# 65c02.net
KiCad netlist of a schematic drawn in Altium Designer
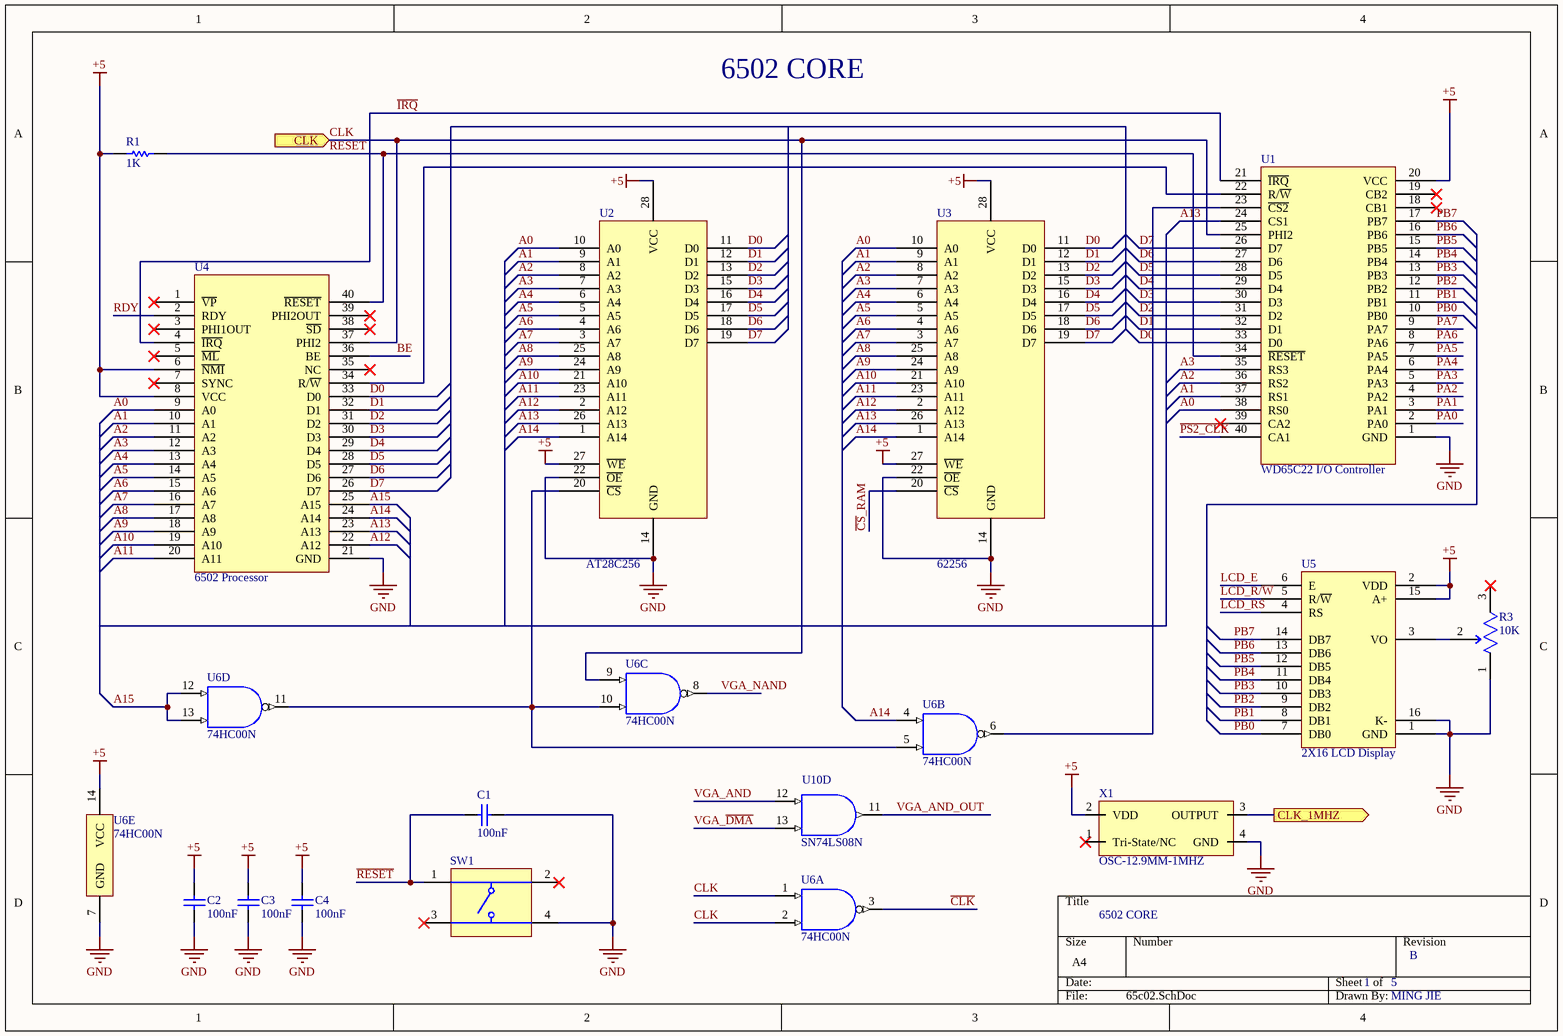
[diagram p0: 65c02.SchDoc]

(export (version "E")
  (design (tool "Eeschema 10.0.6"))
  (components
    (comp (ref "C1")
      (value "GRM21BR71H104KA01L")
      (footprint "CAPC2013X135X45ML10T25")
      (description "Chip Capacitor, 0.1 uF, +/- 10%, 50 V, -55 to 125 degC, 0805 (2012 Metric), RoHS, Tape and Reel")
      (fields
        (field (name "VOLTAGE") "50V")
        (field (name "CAPACITANCE") "100nF")
        (field (name "TOLERANCE") "10%")
      )
      (libsource (lib "Altium Content Vault") (part "CAP-NP-2"))
    )
    (comp (ref "C2")
      (value "GRM21BR71H104KA01L")
      (footprint "CAPC2013X135X45ML10T25")
      (description "Chip Capacitor, 0.1 uF, +/- 10%, 50 V, -55 to 125 degC, 0805 (2012 Metric), RoHS, Tape and Reel")
      (fields
        (field (name "VOLTAGE") "50V")
        (field (name "CAPACITANCE") "100nF")
        (field (name "TOLERANCE") "10%")
      )
      (libsource (lib "Altium Content Vault") (part "CAP-NP-2"))
    )
    (comp (ref "C3")
      (value "GRM21BR71H104KA01L")
      (footprint "CAPC2013X135X45ML10T25")
      (description "Chip Capacitor, 0.1 uF, +/- 10%, 50 V, -55 to 125 degC, 0805 (2012 Metric), RoHS, Tape and Reel")
      (fields
        (field (name "VOLTAGE") "50V")
        (field (name "CAPACITANCE") "100nF")
        (field (name "TOLERANCE") "10%")
      )
      (libsource (lib "Altium Content Vault") (part "CAP-NP-2"))
    )
    (comp (ref "C4")
      (value "GRM21BR71H104KA01L")
      (footprint "CAPC2013X135X45ML10T25")
      (description "Chip Capacitor, 0.1 uF, +/- 10%, 50 V, -55 to 125 degC, 0805 (2012 Metric), RoHS, Tape and Reel")
      (fields
        (field (name "VOLTAGE") "50V")
        (field (name "CAPACITANCE") "100nF")
        (field (name "TOLERANCE") "10%")
      )
      (libsource (lib "Altium Content Vault") (part "CAP-NP-2"))
    )
    (comp (ref "R1")
      (value "CRCW08051K00FKEA")
      (footprint "RESC2013X50X30NL20T20")
      (fields (field (name "MANUFACTURER") "Vishay Dale") (field (name "RESISTANCE") "1K"))
      (libsource (lib "Altium Content Vault") (part "RES"))
    )
    (comp (ref "R3")
      (value "3296W-1-103RLF")
      (footprint "FP-3296W-MFG")
      (description "TRIMMER 10K OHM 0.5W PC PIN TOP")
      (fields (field (name "RESISTANCE") "10K") (field (name "TOLERANCE") "10%"))
      (libsource (lib "Altium Content Vault") (part "194907ebf2981c0cdd5d9631a0af656"))
    )
    (comp (ref "SW1")
      (value "K2-1102SP-C4SC-04")
      (footprint "TECO-FSM4JSMA_V")
      (description "Swicth, SPST, 24 V, -35 to 85 degC, 4-Pin SMD, RoHS, Tape and Reel")
      (fields (field (name "MANUFACTURER") "TE Connectivity"))
      (libsource (lib "Altium Content Vault") (part "SW-SPST-4_A"))
    )
    (comp (ref "U1")
      (value "WD65C22 I/O Controller")
      (footprint "PDIP_40")
      (description "WD65C22 PDIP-40, I/O Controller")
      (libsource (lib "6502_lib") (part "WD65C22"))
    )
    (comp (ref "U2")
      (value "AT28C256")
      (footprint "DIP_28")
      (description "Paged Parallel EEPROM AT28C256")
      (libsource (lib "6502_lib") (part "AT28C256"))
    )
    (comp (ref "U3")
      (value "62256")
      (footprint "DIP_28")
      (description "32K x 8, SRAM")
      (libsource (lib "6502_lib") (part "62256"))
    )
    (comp (ref "U4")
      (value "6502 Processor")
      (footprint "PDIP_40")
      (description "WDC 6502 PDIP-40")
      (libsource (lib "6502_lib") (part "WDC65C02"))
    )
    (comp (ref "U5")
      (value "2X16 LCD Display")
      (footprint "LCD_2x16")
      (description "2X16 LCD Display, Parallel input")
      (libsource (lib "6502_lib") (part "LCM1602C"))
    )
    (comp (ref "U6")
      (value "74HC00N")
      (footprint "NXP-SOT27-1-14")
      (description "Quad 2-input NAND gate, CMOS, 2 to 6 V, -40 to 125 degC, 14-Pin DIP (SOT27-1), RoHS, Bulk")
      (fields (field (name "MANUFACTURER") "NXP Semiconductors"))
      (libsource (lib "") (part "NXP-74HC00N_HCT00N-DIP-14_1"))
    )
    (comp (ref "U10")
      (value "SN74LS08N")
      (footprint "N0014A")
      (description "Quadruple 2-Input Positive-AND Gates, N0014A, TUBE")
      (fields
        (field (name "MANUFACTURER") "Texas Instruments")
        (field (name "GENERIC PART NUMBER") "SN74LS08")
      )
      (libsource (lib "Altium Content Vault") (part "TI-AND-4-2IN-14"))
    )
    (comp (ref "X1")
      (value "OSC-12.9MM-1MHZ")
      (footprint "OSC_THT_12-9MM")
      (description "12.9MM x 12.9MM, 1MHz Can Oscillator")
      (libsource (lib "6502_lib") (part "OSC-12.9MM-1MHZ"))
    )
  )
  (nets
    (net (code "1") (name "+5") (class "Default")
      (node (ref "C2") (pin "1") (pinfunction "1_1") (pintype "passive"))
      (node (ref "C3") (pin "1") (pinfunction "1_1") (pintype "passive"))
      (node (ref "C4") (pin "1") (pinfunction "1_1") (pintype "passive"))
      (node (ref "R1") (pin "1") (pinfunction "1_1") (pintype "passive"))
      (node (ref "U1") (pin "20") (pinfunction "VCC_20") (pintype "passive"))
      (node (ref "U2") (pin "27") (pinfunction "~{WE}_27") (pintype "passive"))
      (node (ref "U2") (pin "28") (pinfunction "VCC_28") (pintype "passive"))
      (node (ref "U3") (pin "27") (pinfunction "~{WE}_27") (pintype "passive"))
      (node (ref "U3") (pin "28") (pinfunction "VCC_28") (pintype "passive"))
      (node (ref "U4") (pin "6") (pinfunction "~{NMI}_6") (pintype "passive"))
      (node (ref "U4") (pin "8") (pinfunction "VCC_8") (pintype "passive"))
      (node (ref "U5") (pin "15") (pinfunction "A+_15") (pintype "passive"))
      (node (ref "U5") (pin "2") (pinfunction "VDD_2") (pintype "passive"))
      (node (ref "U6") (pin "14") (pinfunction "VCC_14") (pintype "power_in"))
      (node (ref "X1") (pin "2") (pinfunction "VDD_2") (pintype "passive"))
    )
    (net (code "2") (name "/A0") (class "Default")
      (node (ref "U1") (pin "38") (pinfunction "RS0_38") (pintype "passive"))
      (node (ref "U2") (pin "10") (pinfunction "A0_10") (pintype "passive"))
      (node (ref "U3") (pin "10") (pinfunction "A0_10") (pintype "passive"))
      (node (ref "U4") (pin "9") (pinfunction "A0_9") (pintype "passive"))
    )
    (net (code "3") (name "/A1") (class "Default")
      (node (ref "U1") (pin "37") (pinfunction "RS1_37") (pintype "passive"))
      (node (ref "U2") (pin "9") (pinfunction "A1_9") (pintype "passive"))
      (node (ref "U3") (pin "9") (pinfunction "A1_9") (pintype "passive"))
      (node (ref "U4") (pin "10") (pinfunction "A1_10") (pintype "passive"))
    )
    (net (code "4") (name "/A2") (class "Default")
      (node (ref "U1") (pin "36") (pinfunction "RS2_36") (pintype "passive"))
      (node (ref "U2") (pin "8") (pinfunction "A2_8") (pintype "passive"))
      (node (ref "U3") (pin "8") (pinfunction "A2_8") (pintype "passive"))
      (node (ref "U4") (pin "11") (pinfunction "A2_11") (pintype "passive"))
    )
    (net (code "5") (name "/A3") (class "Default")
      (node (ref "U1") (pin "35") (pinfunction "RS3_35") (pintype "passive"))
      (node (ref "U2") (pin "7") (pinfunction "A3_7") (pintype "passive"))
      (node (ref "U3") (pin "7") (pinfunction "A3_7") (pintype "passive"))
      (node (ref "U4") (pin "12") (pinfunction "A3_12") (pintype "passive"))
    )
    (net (code "6") (name "/A4") (class "Default")
      (node (ref "U2") (pin "6") (pinfunction "A4_6") (pintype "passive"))
      (node (ref "U3") (pin "6") (pinfunction "A4_6") (pintype "passive"))
      (node (ref "U4") (pin "13") (pinfunction "A4_13") (pintype "passive"))
    )
    (net (code "7") (name "/A5") (class "Default")
      (node (ref "U2") (pin "5") (pinfunction "A5_5") (pintype "passive"))
      (node (ref "U3") (pin "5") (pinfunction "A5_5") (pintype "passive"))
      (node (ref "U4") (pin "14") (pinfunction "A5_14") (pintype "passive"))
    )
    (net (code "8") (name "/A6") (class "Default")
      (node (ref "U2") (pin "4") (pinfunction "A6_4") (pintype "passive"))
      (node (ref "U3") (pin "4") (pinfunction "A6_4") (pintype "passive"))
      (node (ref "U4") (pin "15") (pinfunction "A6_15") (pintype "passive"))
    )
    (net (code "9") (name "/A7") (class "Default")
      (node (ref "U2") (pin "3") (pinfunction "A7_3") (pintype "passive"))
      (node (ref "U3") (pin "3") (pinfunction "A7_3") (pintype "passive"))
      (node (ref "U4") (pin "16") (pinfunction "A7_16") (pintype "passive"))
    )
    (net (code "10") (name "/A8") (class "Default")
      (node (ref "U2") (pin "25") (pinfunction "A8_25") (pintype "passive"))
      (node (ref "U3") (pin "25") (pinfunction "A8_25") (pintype "passive"))
      (node (ref "U4") (pin "17") (pinfunction "A8_17") (pintype "passive"))
    )
    (net (code "11") (name "/A9") (class "Default")
      (node (ref "U2") (pin "24") (pinfunction "A9_24") (pintype "passive"))
      (node (ref "U3") (pin "24") (pinfunction "A9_24") (pintype "passive"))
      (node (ref "U4") (pin "18") (pinfunction "A9_18") (pintype "passive"))
    )
    (net (code "12") (name "/A10") (class "Default")
      (node (ref "U2") (pin "21") (pinfunction "A10_21") (pintype "passive"))
      (node (ref "U3") (pin "21") (pinfunction "A10_21") (pintype "passive"))
      (node (ref "U4") (pin "19") (pinfunction "A10_19") (pintype "passive"))
    )
    (net (code "13") (name "/A11") (class "Default")
      (node (ref "U2") (pin "23") (pinfunction "A11_23") (pintype "passive"))
      (node (ref "U3") (pin "23") (pinfunction "A11_23") (pintype "passive"))
      (node (ref "U4") (pin "20") (pinfunction "A11_20") (pintype "passive"))
    )
    (net (code "14") (name "/A12") (class "Default")
      (node (ref "U2") (pin "2") (pinfunction "A12_2") (pintype "passive"))
      (node (ref "U3") (pin "2") (pinfunction "A12_2") (pintype "passive"))
      (node (ref "U4") (pin "22") (pinfunction "A12_22") (pintype "passive"))
    )
    (net (code "15") (name "/A13") (class "Default")
      (node (ref "U1") (pin "24") (pinfunction "CS1_24") (pintype "passive"))
      (node (ref "U2") (pin "26") (pinfunction "A13_26") (pintype "passive"))
      (node (ref "U3") (pin "26") (pinfunction "A13_26") (pintype "passive"))
      (node (ref "U4") (pin "23") (pinfunction "A13_23") (pintype "passive"))
    )
    (net (code "16") (name "/A14") (class "Default")
      (node (ref "U2") (pin "1") (pinfunction "A14_1") (pintype "passive"))
      (node (ref "U3") (pin "1") (pinfunction "A14_1") (pintype "passive"))
      (node (ref "U4") (pin "24") (pinfunction "A14_24") (pintype "passive"))
      (node (ref "U6") (pin "4") (pinfunction "2A_4") (pintype "input"))
    )
    (net (code "17") (name "/A15") (class "Default")
      (node (ref "U4") (pin "25") (pinfunction "A15_25") (pintype "passive"))
      (node (ref "U6") (pin "12") (pinfunction "4A_12") (pintype "input"))
      (node (ref "U6") (pin "13") (pinfunction "4B_13") (pintype "input"))
    )
    (net (code "18") (name "/BE") (class "Default")
      (node (ref "U4") (pin "36") (pinfunction "BE_36") (pintype "passive"))
    )
    (net (code "19") (name "/CLK") (class "Default")
      (node (ref "U1") (pin "25") (pinfunction "PHI2_25") (pintype "passive"))
      (node (ref "U4") (pin "37") (pinfunction "PHI2_37") (pintype "passive"))
      (node (ref "U6") (pin "1") (pinfunction "1A_1") (pintype "input"))
      (node (ref "U6") (pin "2") (pinfunction "1B_2") (pintype "input"))
      (node (ref "U6") (pin "9") (pinfunction "3A_9") (pintype "input"))
    )
    (net (code "20") (name "/CLK_1MHZ") (class "Default")
      (node (ref "X1") (pin "3") (pinfunction "OUTPUT_3") (pintype "passive"))
    )
    (net (code "21") (name "/D0") (class "Default")
      (node (ref "U1") (pin "33") (pinfunction "D0_33") (pintype "passive"))
      (node (ref "U2") (pin "11") (pinfunction "D0_11") (pintype "passive"))
      (node (ref "U3") (pin "11") (pinfunction "D0_11") (pintype "passive"))
      (node (ref "U4") (pin "33") (pinfunction "D0_33") (pintype "passive"))
    )
    (net (code "22") (name "/D1") (class "Default")
      (node (ref "U1") (pin "32") (pinfunction "D1_32") (pintype "passive"))
      (node (ref "U2") (pin "12") (pinfunction "D1_12") (pintype "passive"))
      (node (ref "U3") (pin "12") (pinfunction "D1_12") (pintype "passive"))
      (node (ref "U4") (pin "32") (pinfunction "D1_32") (pintype "passive"))
    )
    (net (code "23") (name "/D2") (class "Default")
      (node (ref "U1") (pin "31") (pinfunction "D2_31") (pintype "passive"))
      (node (ref "U2") (pin "13") (pinfunction "D2_13") (pintype "passive"))
      (node (ref "U3") (pin "13") (pinfunction "D2_13") (pintype "passive"))
      (node (ref "U4") (pin "31") (pinfunction "D2_31") (pintype "passive"))
    )
    (net (code "24") (name "/D3") (class "Default")
      (node (ref "U1") (pin "30") (pinfunction "D3_30") (pintype "passive"))
      (node (ref "U2") (pin "15") (pinfunction "D3_15") (pintype "passive"))
      (node (ref "U3") (pin "15") (pinfunction "D3_15") (pintype "passive"))
      (node (ref "U4") (pin "30") (pinfunction "D3_30") (pintype "passive"))
    )
    (net (code "25") (name "/D4") (class "Default")
      (node (ref "U1") (pin "29") (pinfunction "D4_29") (pintype "passive"))
      (node (ref "U2") (pin "16") (pinfunction "D4_16") (pintype "passive"))
      (node (ref "U3") (pin "16") (pinfunction "D4_16") (pintype "passive"))
      (node (ref "U4") (pin "29") (pinfunction "D4_29") (pintype "passive"))
    )
    (net (code "26") (name "/D5") (class "Default")
      (node (ref "U1") (pin "28") (pinfunction "D5_28") (pintype "passive"))
      (node (ref "U2") (pin "17") (pinfunction "D5_17") (pintype "passive"))
      (node (ref "U3") (pin "17") (pinfunction "D5_17") (pintype "passive"))
      (node (ref "U4") (pin "28") (pinfunction "D5_28") (pintype "passive"))
    )
    (net (code "27") (name "/D6") (class "Default")
      (node (ref "U1") (pin "27") (pinfunction "D6_27") (pintype "passive"))
      (node (ref "U2") (pin "18") (pinfunction "D6_18") (pintype "passive"))
      (node (ref "U3") (pin "18") (pinfunction "D6_18") (pintype "passive"))
      (node (ref "U4") (pin "27") (pinfunction "D6_27") (pintype "passive"))
    )
    (net (code "28") (name "/D7") (class "Default")
      (node (ref "U1") (pin "26") (pinfunction "D7_26") (pintype "passive"))
      (node (ref "U2") (pin "19") (pinfunction "D7_19") (pintype "passive"))
      (node (ref "U3") (pin "19") (pinfunction "D7_19") (pintype "passive"))
      (node (ref "U4") (pin "26") (pinfunction "D7_26") (pintype "passive"))
    )
    (net (code "29") (name "/LCD_E") (class "Default")
      (node (ref "U5") (pin "6") (pinfunction "E_6") (pintype "passive"))
    )
    (net (code "30") (name "/LCD_RS") (class "Default")
      (node (ref "U5") (pin "4") (pinfunction "RS_4") (pintype "passive"))
    )
    (net (code "31") (name "/LCD_R{slash}~{W}") (class "Default")
      (node (ref "U5") (pin "5") (pinfunction "R/~{W}_5") (pintype "passive"))
    )
    (net (code "32") (name "/PA0") (class "Default")
      (node (ref "U1") (pin "2") (pinfunction "PA0_2") (pintype "passive"))
    )
    (net (code "33") (name "/PA1") (class "Default")
      (node (ref "U1") (pin "3") (pinfunction "PA1_3") (pintype "passive"))
    )
    (net (code "34") (name "/PA2") (class "Default")
      (node (ref "U1") (pin "4") (pinfunction "PA2_4") (pintype "passive"))
    )
    (net (code "35") (name "/PA3") (class "Default")
      (node (ref "U1") (pin "5") (pinfunction "PA3_5") (pintype "passive"))
    )
    (net (code "36") (name "/PA4") (class "Default")
      (node (ref "U1") (pin "6") (pinfunction "PA4_6") (pintype "passive"))
    )
    (net (code "37") (name "/PA5") (class "Default")
      (node (ref "U1") (pin "7") (pinfunction "PA5_7") (pintype "passive"))
    )
    (net (code "38") (name "/PA6") (class "Default")
      (node (ref "U1") (pin "8") (pinfunction "PA6_8") (pintype "passive"))
    )
    (net (code "39") (name "/PA7") (class "Default")
      (node (ref "U1") (pin "9") (pinfunction "PA7_9") (pintype "passive"))
    )
    (net (code "40") (name "/PB0") (class "Default")
      (node (ref "U1") (pin "10") (pinfunction "PB0_10") (pintype "passive"))
      (node (ref "U5") (pin "7") (pinfunction "DB0_7") (pintype "passive"))
    )
    (net (code "41") (name "/PB1") (class "Default")
      (node (ref "U1") (pin "11") (pinfunction "PB1_11") (pintype "passive"))
      (node (ref "U5") (pin "8") (pinfunction "DB1_8") (pintype "passive"))
    )
    (net (code "42") (name "/PB2") (class "Default")
      (node (ref "U1") (pin "12") (pinfunction "PB2_12") (pintype "passive"))
      (node (ref "U5") (pin "9") (pinfunction "DB2_9") (pintype "passive"))
    )
    (net (code "43") (name "/PB3") (class "Default")
      (node (ref "U1") (pin "13") (pinfunction "PB3_13") (pintype "passive"))
      (node (ref "U5") (pin "10") (pinfunction "DB3_10") (pintype "passive"))
    )
    (net (code "44") (name "/PB4") (class "Default")
      (node (ref "U1") (pin "14") (pinfunction "PB4_14") (pintype "passive"))
      (node (ref "U5") (pin "11") (pinfunction "DB4_11") (pintype "passive"))
    )
    (net (code "45") (name "/PB5") (class "Default")
      (node (ref "U1") (pin "15") (pinfunction "PB5_15") (pintype "passive"))
      (node (ref "U5") (pin "12") (pinfunction "DB5_12") (pintype "passive"))
    )
    (net (code "46") (name "/PB6") (class "Default")
      (node (ref "U1") (pin "16") (pinfunction "PB6_16") (pintype "passive"))
      (node (ref "U5") (pin "13") (pinfunction "DB6_13") (pintype "passive"))
    )
    (net (code "47") (name "/PB7") (class "Default")
      (node (ref "U1") (pin "17") (pinfunction "PB7_17") (pintype "passive"))
      (node (ref "U5") (pin "14") (pinfunction "DB7_14") (pintype "passive"))
    )
    (net (code "48") (name "/RDY") (class "Default")
      (node (ref "U4") (pin "2") (pinfunction "RDY_2") (pintype "passive"))
    )
    (net (code "49") (name "/VGA_AND") (class "Default")
      (node (ref "U10") (pin "12") (pinfunction "4A_12") (pintype "input"))
    )
    (net (code "50") (name "/VGA_AND_OUT") (class "Default")
      (node (ref "U10") (pin "11") (pinfunction "4Y_11") (pintype "output"))
    )
    (net (code "51") (name "/VGA_NAND") (class "Default")
      (node (ref "U6") (pin "8") (pinfunction "~{3Y}_8") (pintype "output"))
    )
    (net (code "52") (name "/VGA_~{DMA}") (class "Default")
      (node (ref "U10") (pin "13") (pinfunction "4B_13") (pintype "input"))
    )
    (net (code "53") (name "/~{CLK}") (class "Default")
      (node (ref "U6") (pin "3") (pinfunction "~{1Y}_3") (pintype "output"))
    )
    (net (code "54") (name "/~{CS}_RAM") (class "Default")
      (node (ref "U3") (pin "20") (pinfunction "~{CS}_20") (pintype "passive"))
    )
    (net (code "55") (name "/~{IRQ}") (class "Default")
      (node (ref "U1") (pin "21") (pinfunction "~{IRQ}_21") (pintype "passive"))
      (node (ref "U4") (pin "4") (pinfunction "~{IRQ}_4") (pintype "passive"))
    )
    (net (code "56") (name "/~{PS2_CLK}") (class "Default")
      (node (ref "U1") (pin "40") (pinfunction "CA1_40") (pintype "passive"))
    )
    (net (code "57") (name "/~{RESET}") (class "Default")
      (node (ref "C1") (pin "2") (pinfunction "2_2") (pintype "passive"))
      (node (ref "R1") (pin "2") (pinfunction "2_2") (pintype "passive"))
      (node (ref "SW1") (pin "1") (pinfunction "1_1") (pintype "passive"))
      (node (ref "U1") (pin "34") (pinfunction "~{RESET}_34") (pintype "passive"))
      (node (ref "U4") (pin "40") (pinfunction "~{RESET}_40") (pintype "passive"))
    )
    (net (code "58") (name "GND") (class "Default")
      (node (ref "C1") (pin "1") (pinfunction "1_1") (pintype "passive"))
      (node (ref "C2") (pin "2") (pinfunction "2_2") (pintype "passive"))
      (node (ref "C3") (pin "2") (pinfunction "2_2") (pintype "passive"))
      (node (ref "C4") (pin "2") (pinfunction "2_2") (pintype "passive"))
      (node (ref "R3") (pin "1") (pinfunction "CCW_1") (pintype "passive"))
      (node (ref "SW1") (pin "4") (pinfunction "4_4") (pintype "passive"))
      (node (ref "U1") (pin "1") (pinfunction "GND_1") (pintype "passive"))
      (node (ref "U2") (pin "14") (pinfunction "GND_14") (pintype "passive"))
      (node (ref "U2") (pin "22") (pinfunction "~{OE}_22") (pintype "passive"))
      (node (ref "U3") (pin "14") (pinfunction "GND_14") (pintype "passive"))
      (node (ref "U3") (pin "22") (pinfunction "~{OE}_22") (pintype "passive"))
      (node (ref "U4") (pin "21") (pinfunction "GND_21") (pintype "passive"))
      (node (ref "U5") (pin "1") (pinfunction "GND_1") (pintype "passive"))
      (node (ref "U5") (pin "16") (pinfunction "K-_16") (pintype "passive"))
      (node (ref "U6") (pin "7") (pinfunction "GND_7") (pintype "power_in"))
      (node (ref "X1") (pin "4") (pinfunction "GND_4") (pintype "passive"))
    )
    (net (code "59") (name "Net-(R3-WIPER)") (class "Default")
      (node (ref "R3") (pin "2") (pinfunction "WIPER_2") (pintype "passive"))
      (node (ref "U5") (pin "3") (pinfunction "VO_3") (pintype "passive"))
    )
    (net (code "60") (name "Net-(U1-R{slash}~{W})") (class "Default")
      (node (ref "U1") (pin "22") (pinfunction "R/~{W}_22") (pintype "passive"))
      (node (ref "U4") (pin "34") (pinfunction "R/~{W}_34") (pintype "passive"))
    )
    (net (code "61") (name "Net-(U1-~{CS2})") (class "Default")
      (node (ref "U1") (pin "23") (pinfunction "~{CS2}_23") (pintype "passive"))
      (node (ref "U6") (pin "6") (pinfunction "~{2Y}_6") (pintype "output"))
    )
    (net (code "62") (name "Net-(U2-~{CS})") (class "Default")
      (node (ref "U2") (pin "20") (pinfunction "~{CS}_20") (pintype "passive"))
      (node (ref "U6") (pin "10") (pinfunction "3B_10") (pintype "input"))
      (node (ref "U6") (pin "11") (pinfunction "~{4Y}_11") (pintype "output"))
      (node (ref "U6") (pin "5") (pinfunction "2B_5") (pintype "input"))
    )
    (net (code "63") (name "unconnected-(R3-CW-Pad3)") (class "Default")
      (node (ref "R3") (pin "3") (pinfunction "CW_3") (pintype "passive+no_connect"))
    )
    (net (code "64") (name "unconnected-(SW1-Pad2)") (class "Default")
      (node (ref "SW1") (pin "2") (pinfunction "2_2") (pintype "passive+no_connect"))
    )
    (net (code "65") (name "unconnected-(SW1-Pad3)") (class "Default")
      (node (ref "SW1") (pin "3") (pinfunction "3_3") (pintype "passive+no_connect"))
    )
    (net (code "66") (name "unconnected-(U1-CA2-Pad39)") (class "Default")
      (node (ref "U1") (pin "39") (pinfunction "CA2_39") (pintype "passive+no_connect"))
    )
    (net (code "67") (name "unconnected-(U1-CB1-Pad18)") (class "Default")
      (node (ref "U1") (pin "18") (pinfunction "CB1_18") (pintype "passive+no_connect"))
    )
    (net (code "68") (name "unconnected-(U1-CB2-Pad19)") (class "Default")
      (node (ref "U1") (pin "19") (pinfunction "CB2_19") (pintype "passive+no_connect"))
    )
    (net (code "69") (name "unconnected-(U4-NC-Pad35)") (class "Default")
      (node (ref "U4") (pin "35") (pinfunction "NC_35") (pintype "passive+no_connect"))
    )
    (net (code "70") (name "unconnected-(U4-PHI1OUT-Pad3)") (class "Default")
      (node (ref "U4") (pin "3") (pinfunction "PHI1OUT_3") (pintype "passive+no_connect"))
    )
    (net (code "71") (name "unconnected-(U4-PHI2OUT-Pad39)") (class "Default")
      (node (ref "U4") (pin "39") (pinfunction "PHI2OUT_39") (pintype "passive+no_connect"))
    )
    (net (code "72") (name "unconnected-(U4-SYNC-Pad7)") (class "Default")
      (node (ref "U4") (pin "7") (pinfunction "SYNC_7") (pintype "passive+no_connect"))
    )
    (net (code "73") (name "unconnected-(U4-~{ML}-Pad5)") (class "Default")
      (node (ref "U4") (pin "5") (pinfunction "~{ML}_5") (pintype "passive+no_connect"))
    )
    (net (code "74") (name "unconnected-(U4-~{SD}-Pad38)") (class "Default")
      (node (ref "U4") (pin "38") (pinfunction "~{SD}_38") (pintype "passive+no_connect"))
    )
    (net (code "75") (name "unconnected-(U4-~{VP}-Pad1)") (class "Default")
      (node (ref "U4") (pin "1") (pinfunction "~{VP}_1") (pintype "passive+no_connect"))
    )
    (net (code "76") (name "unconnected-(X1-Tri-State{slash}NC-Pad1)") (class "Default")
      (node (ref "X1") (pin "1") (pinfunction "Tri-State/NC_1") (pintype "passive+no_connect"))
    )
  )
)
